# CAN2.net
KiCad netlist of a schematic drawn in Altium Designer
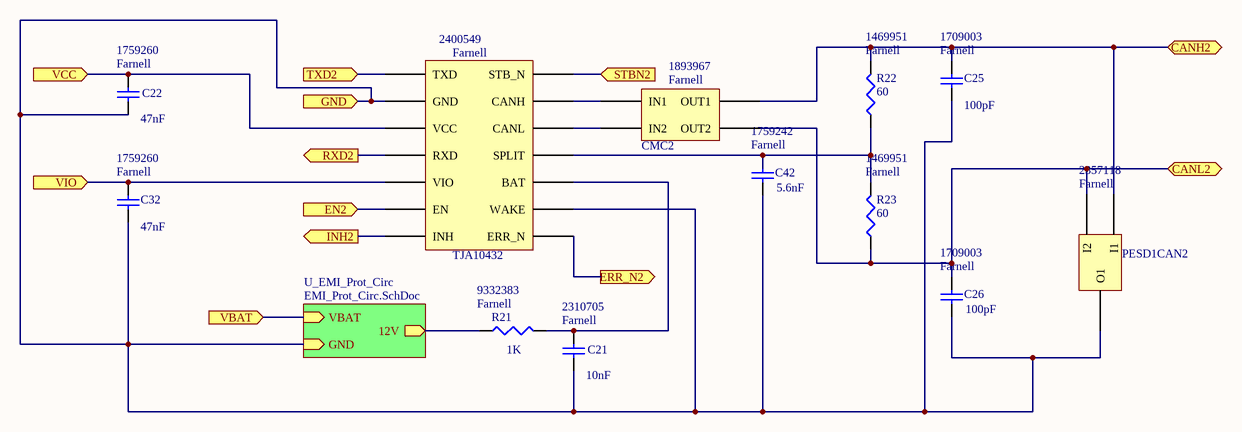
[diagram p0: CAN2.SchDoc]

(export (version "E")
  (design (tool "Eeschema 10.0.6"))
  (components
    (comp (ref "C21")
      (value "10nF")
      (footprint "CAP_0805")
      (description "Capacitor")
      (fields
        (field (name "SUPPLIER 1") "Farnell")
        (field (name "SUPPLIER PART NUMBER 1") "2310705")
        (field (name "Comment") "10n")
        (field (name "PUBLISHER") "Altium Limited")
      )
      (libsource (lib "Miscellaneous Devices") (part "Cap Semi"))
    )
    (comp (ref "C22")
      (value "47nF")
      (footprint "CAP_0805")
      (description "Capacitor")
      (fields
        (field (name "SUPPLIER 1") "Farnell")
        (field (name "SUPPLIER PART NUMBER 1") "1759260")
        (field (name "Comment") "47n")
        (field (name "PUBLISHER") "Altium Limited")
      )
      (libsource (lib "Miscellaneous Devices") (part "Cap Semi"))
    )
    (comp (ref "C25")
      (value "100pF")
      (footprint "CAP_0805")
      (description "Capacitor")
      (fields
        (field (name "SUPPLIER 1") "Farnell")
        (field (name "SUPPLIER PART NUMBER 1") "1709003")
        (field (name "Comment") "100p")
        (field (name "PUBLISHER") "Altium Limited")
      )
      (libsource (lib "Miscellaneous Devices") (part "Cap Semi"))
    )
    (comp (ref "C26")
      (value "100pF")
      (footprint "CAP_0805")
      (description "Capacitor")
      (fields
        (field (name "SUPPLIER 1") "Farnell")
        (field (name "SUPPLIER PART NUMBER 1") "1709003")
        (field (name "Comment") "100p")
        (field (name "PUBLISHER") "Altium Limited")
      )
      (libsource (lib "Miscellaneous Devices") (part "Cap Semi"))
    )
    (comp (ref "C32")
      (value "47nF")
      (footprint "CAP_0805")
      (description "Capacitor")
      (fields
        (field (name "SUPPLIER 1") "Farnell")
        (field (name "SUPPLIER PART NUMBER 1") "1759260")
        (field (name "Comment") "47n")
        (field (name "PUBLISHER") "Altium Limited")
      )
      (libsource (lib "Miscellaneous Devices") (part "Cap Semi"))
    )
    (comp (ref "C42")
      (value "5.6nF")
      (footprint "CAP_0805")
      (description "Capacitor")
      (fields
        (field (name "SUPPLIER 1") "Farnell")
        (field (name "SUPPLIER PART NUMBER 1") "1759242")
        (field (name "Comment") "5.6n")
        (field (name "PUBLISHER") "Altium Limited")
      )
      (libsource (lib "Miscellaneous Devices") (part "Cap Semi"))
    )
    (comp (ref "CMC2")
      (value "~")
      (footprint "CMC")
      (description "Common mode choke: DR331-475BE")
      (fields (field (name "SUPPLIER 1") "Farnell") (field (name "SUPPLIER PART NUMBER 1") "1893967"))
      (libsource (lib "Schlib1_HMI3D") (part "Common_Mode_Choke"))
    )
    (comp (ref "PESD1CAN2")
      (value "~")
      (footprint "SOT32-PESD1CAN")
      (description "CAN bus ESD protection diode")
      (fields (field (name "SUPPLIER 1") "Farnell") (field (name "SUPPLIER PART NUMBER 1") "2357118"))
      (libsource (lib "Schlib1_HMI3D") (part "PESD1CAN"))
    )
    (comp (ref "R21")
      (value "1K")
      (footprint "RES_0805")
      (description "Resistor")
      (fields
        (field (name "SUPPLIER 1") "Farnell")
        (field (name "SUPPLIER PART NUMBER 1") "9332383")
        (field (name "Comment") "1k")
        (field (name "PUBLISHER") "Altium Limited")
      )
      (libsource (lib "Miscellaneous Devices") (part "Res3"))
    )
    (comp (ref "R22")
      (value "60")
      (footprint "RES_0805")
      (description "Resistor")
      (fields
        (field (name "SUPPLIER 1") "Farnell")
        (field (name "SUPPLIER PART NUMBER 1") "1469951")
        (field (name "PUBLISHER") "Altium Limited")
      )
      (libsource (lib "Miscellaneous Devices") (part "Res3"))
    )
    (comp (ref "R23")
      (value "60")
      (footprint "RES_0805")
      (description "Resistor")
      (fields
        (field (name "SUPPLIER 1") "Farnell")
        (field (name "SUPPLIER PART NUMBER 1") "1469951")
        (field (name "PUBLISHER") "Altium Limited")
      )
      (libsource (lib "Miscellaneous Devices") (part "Res3"))
    )
    (comp (ref "TJA10432")
      (value "~")
      (footprint "SOIC14-TJA1043")
      (description "CAN transceiver")
      (fields (field (name "SUPPLIER 1") "Farnell") (field (name "SUPPLIER PART NUMBER 1") "2400549"))
      (libsource (lib "Schlib1_HMI3D") (part "TJA1043"))
    )
  )
  (nets
    (net (code "1") (name "/12V") (class "Default")
      (node (ref "R21") (pin "1") (pinfunction "1_1") (pintype "passive"))
    )
    (net (code "2") (name "/CANH2") (class "Default")
      (node (ref "C25") (pin "2") (pinfunction "2_2") (pintype "passive"))
      (node (ref "CMC2") (pin "OUT1") (pinfunction "OUT1_OUT1") (pintype "passive"))
      (node (ref "PESD1CAN2") (pin "I1") (pinfunction "I1_I1") (pintype "passive"))
      (node (ref "R22") (pin "2") (pinfunction "2_2") (pintype "passive"))
    )
    (net (code "3") (name "/CANL2") (class "Default")
      (node (ref "C26") (pin "2") (pinfunction "2_2") (pintype "passive"))
      (node (ref "CMC2") (pin "OUT2") (pinfunction "OUT2_OUT2") (pintype "passive"))
      (node (ref "PESD1CAN2") (pin "I2") (pinfunction "I2_I2") (pintype "passive"))
      (node (ref "R23") (pin "1") (pinfunction "1_1") (pintype "passive"))
    )
    (net (code "4") (name "/EN2") (class "Default")
      (node (ref "TJA10432") (pin "EN") (pinfunction "EN_EN") (pintype "passive"))
    )
    (net (code "5") (name "/ERR_N2") (class "Default")
      (node (ref "TJA10432") (pin "ERR_N") (pinfunction "ERR_N_ERR_N") (pintype "passive"))
    )
    (net (code "6") (name "/GND") (class "Default")
      (node (ref "C21") (pin "1") (pinfunction "1_1") (pintype "passive"))
      (node (ref "C22") (pin "1") (pinfunction "1_1") (pintype "passive"))
      (node (ref "C25") (pin "1") (pinfunction "1_1") (pintype "passive"))
      (node (ref "C26") (pin "1") (pinfunction "1_1") (pintype "passive"))
      (node (ref "C32") (pin "1") (pinfunction "1_1") (pintype "passive"))
      (node (ref "C42") (pin "1") (pinfunction "1_1") (pintype "passive"))
      (node (ref "PESD1CAN2") (pin "O1") (pinfunction "O1_O1") (pintype "passive"))
      (node (ref "TJA10432") (pin "GND") (pinfunction "GND_GND") (pintype "passive"))
      (node (ref "TJA10432") (pin "WAKE") (pinfunction "WAKE_WAKE") (pintype "passive"))
    )
    (net (code "7") (name "/INH2") (class "Default")
      (node (ref "TJA10432") (pin "INH") (pinfunction "INH_INH") (pintype "passive"))
    )
    (net (code "8") (name "/RXD2") (class "Default")
      (node (ref "TJA10432") (pin "RXD") (pinfunction "RXD_RXD") (pintype "passive"))
    )
    (net (code "9") (name "/STBN2") (class "Default")
      (node (ref "TJA10432") (pin "STB_N") (pinfunction "STB_N_STB_N") (pintype "passive"))
    )
    (net (code "10") (name "/TXD2") (class "Default")
      (node (ref "TJA10432") (pin "TXD") (pinfunction "TXD_TXD") (pintype "passive"))
    )
    (net (code "12") (name "/VCC") (class "Default")
      (node (ref "C22") (pin "2") (pinfunction "2_2") (pintype "passive"))
      (node (ref "TJA10432") (pin "VCC") (pinfunction "VCC_VCC") (pintype "passive"))
    )
    (net (code "13") (name "/VIO") (class "Default")
      (node (ref "C32") (pin "2") (pinfunction "2_2") (pintype "passive"))
      (node (ref "TJA10432") (pin "VIO") (pinfunction "VIO_VIO") (pintype "passive"))
    )
    (net (code "14") (name "Net-(C21-Pad2)") (class "Default")
      (node (ref "C21") (pin "2") (pinfunction "2_2") (pintype "passive"))
      (node (ref "R21") (pin "2") (pinfunction "2_2") (pintype "passive"))
      (node (ref "TJA10432") (pin "BAT") (pinfunction "BAT_BAT") (pintype "passive"))
    )
    (net (code "15") (name "Net-(C42-Pad2)") (class "Default")
      (node (ref "C42") (pin "2") (pinfunction "2_2") (pintype "passive"))
      (node (ref "R22") (pin "1") (pinfunction "1_1") (pintype "passive"))
      (node (ref "R23") (pin "2") (pinfunction "2_2") (pintype "passive"))
      (node (ref "TJA10432") (pin "SPLIT") (pinfunction "SPLIT_SPLIT") (pintype "passive"))
    )
    (net (code "16") (name "Net-(CMC2-PadIN1)") (class "Default")
      (node (ref "CMC2") (pin "IN1") (pinfunction "IN1_IN1") (pintype "passive"))
      (node (ref "TJA10432") (pin "CANH") (pinfunction "CANH_CANH") (pintype "passive"))
    )
    (net (code "17") (name "Net-(CMC2-PadIN2)") (class "Default")
      (node (ref "CMC2") (pin "IN2") (pinfunction "IN2_IN2") (pintype "passive"))
      (node (ref "TJA10432") (pin "CANL") (pinfunction "CANL_CANL") (pintype "passive"))
    )
  )
)
